# Controller-Board_Rack-PDU_2_1.net
KiCad netlist of a schematic drawn in EAGLE
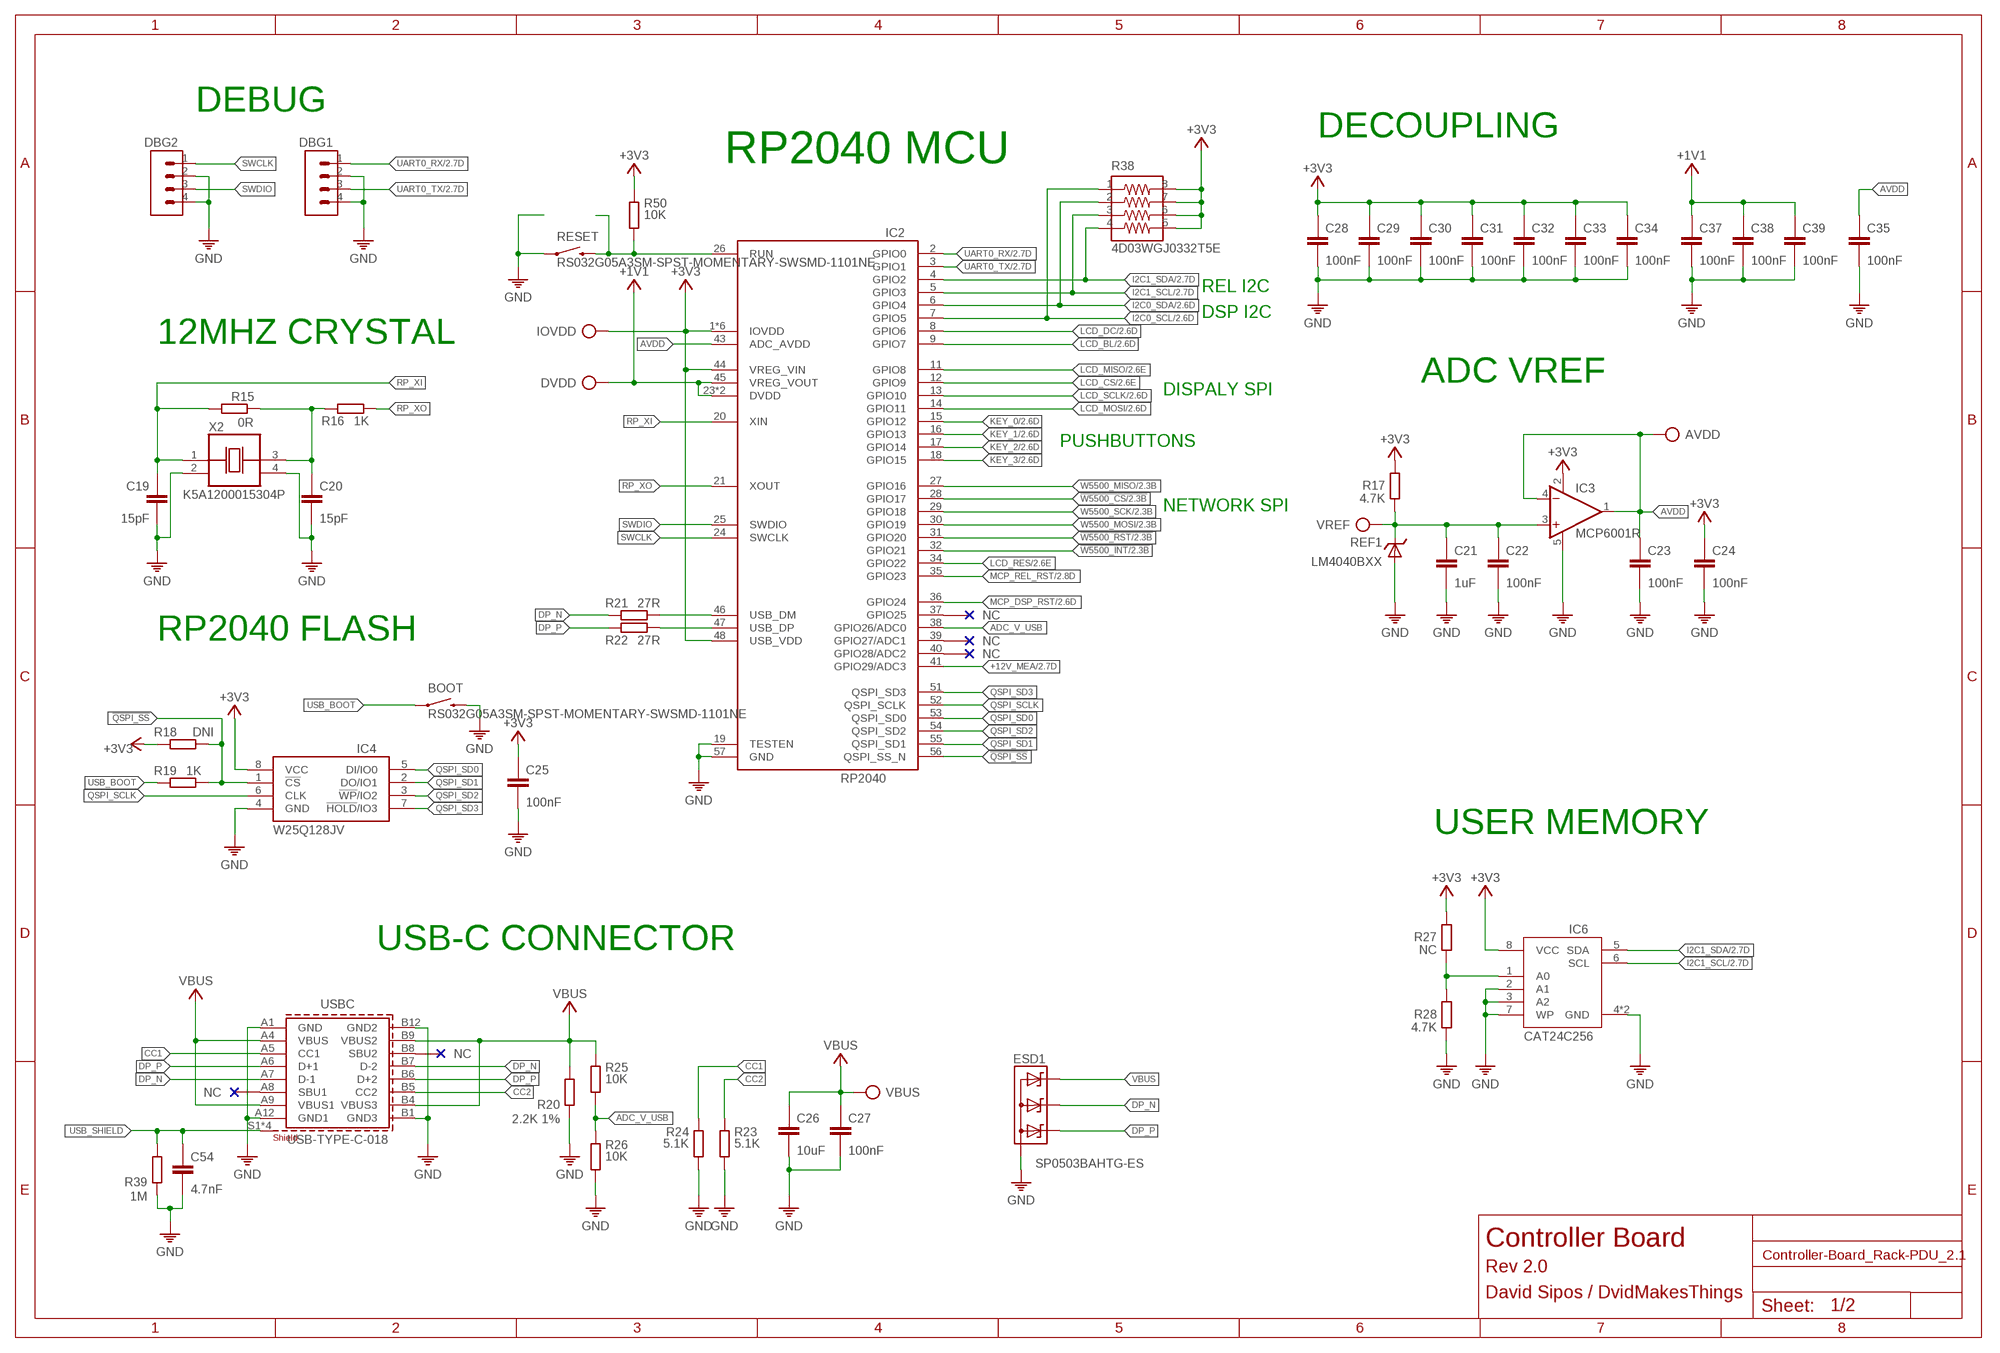
[diagram p0: schematic, sheet 1]
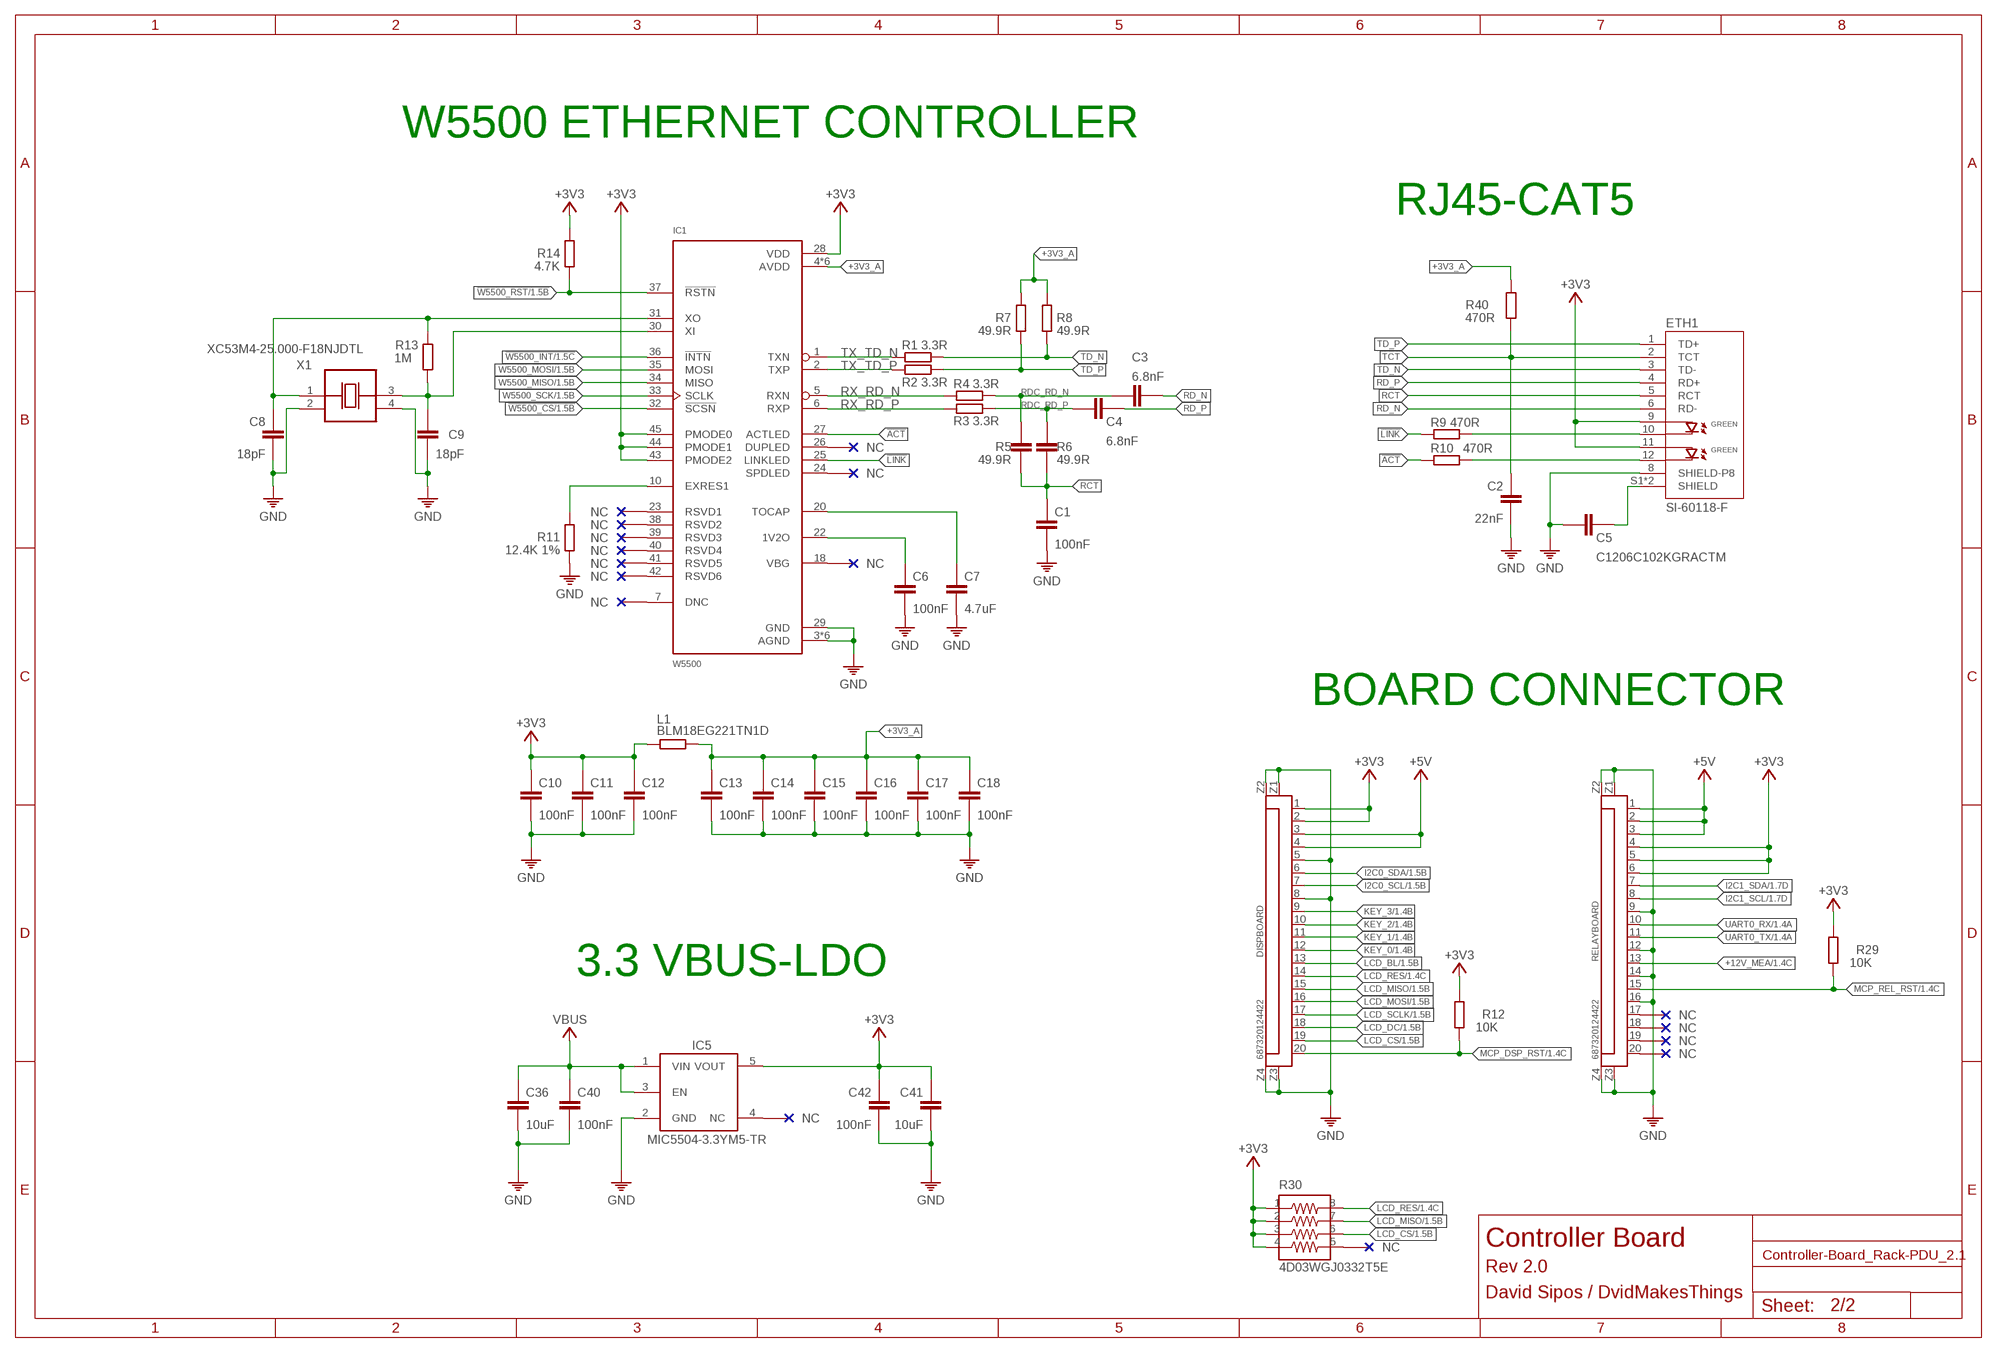
[diagram p1: schematic, sheet 2]

(export (version "E")
  (design (tool "Eeschema 10.0.6"))
  (components
    (comp (ref "C1")
      (value "100nF")
      (footprint "eagle-import:C0402")
      (libsource (lib "eagle-import") (part "C-0402"))
    )
    (comp (ref "C2")
      (value "22nF")
      (footprint "eagle-import:C0402")
      (libsource (lib "eagle-import") (part "C-0402"))
    )
    (comp (ref "C3")
      (value "6.8nF")
      (footprint "eagle-import:C0402")
      (libsource (lib "eagle-import") (part "C-0402"))
    )
    (comp (ref "C4")
      (value "6.8nF")
      (footprint "eagle-import:C0402")
      (libsource (lib "eagle-import") (part "C-0402"))
    )
    (comp (ref "C5")
      (value "C1206C102KGRACTM")
      (footprint "eagle-import:C1206")
      (libsource (lib "eagle-import") (part "C-1206"))
    )
    (comp (ref "C6")
      (value "100nF")
      (footprint "eagle-import:C0402")
      (libsource (lib "eagle-import") (part "C-0402"))
    )
    (comp (ref "C7")
      (value "4.7uF")
      (footprint "eagle-import:C0402")
      (libsource (lib "eagle-import") (part "C-0402"))
    )
    (comp (ref "C8")
      (value "18pF")
      (footprint "eagle-import:C0402")
      (libsource (lib "eagle-import") (part "C-0402"))
    )
    (comp (ref "C9")
      (value "18pF")
      (footprint "eagle-import:C0402")
      (libsource (lib "eagle-import") (part "C-0402"))
    )
    (comp (ref "C10")
      (value "100nF")
      (footprint "eagle-import:C0402")
      (libsource (lib "eagle-import") (part "C-0402"))
    )
    (comp (ref "C11")
      (value "100nF")
      (footprint "eagle-import:C0402")
      (libsource (lib "eagle-import") (part "C-0402"))
    )
    (comp (ref "C12")
      (value "100nF")
      (footprint "eagle-import:C0402")
      (libsource (lib "eagle-import") (part "C-0402"))
    )
    (comp (ref "C13")
      (value "100nF")
      (footprint "eagle-import:C0402")
      (libsource (lib "eagle-import") (part "C-0402"))
    )
    (comp (ref "C14")
      (value "100nF")
      (footprint "eagle-import:C0402")
      (libsource (lib "eagle-import") (part "C-0402"))
    )
    (comp (ref "C15")
      (value "100nF")
      (footprint "eagle-import:C0402")
      (libsource (lib "eagle-import") (part "C-0402"))
    )
    (comp (ref "C16")
      (value "100nF")
      (footprint "eagle-import:C0402")
      (libsource (lib "eagle-import") (part "C-0402"))
    )
    (comp (ref "C17")
      (value "100nF")
      (footprint "eagle-import:C0402")
      (libsource (lib "eagle-import") (part "C-0402"))
    )
    (comp (ref "C18")
      (value "100nF")
      (footprint "eagle-import:C0402")
      (libsource (lib "eagle-import") (part "C-0402"))
    )
    (comp (ref "C36")
      (value "10uF")
      (footprint "eagle-import:0805")
      (libsource (lib "eagle-import") (part "C0805"))
    )
    (comp (ref "C40")
      (value "100nF")
      (footprint "eagle-import:0402")
      (libsource (lib "eagle-import") (part "C0402"))
    )
    (comp (ref "C41")
      (value "10uF")
      (footprint "eagle-import:0805")
      (libsource (lib "eagle-import") (part "C0805"))
    )
    (comp (ref "C42")
      (value "100nF")
      (footprint "eagle-import:0402")
      (libsource (lib "eagle-import") (part "C0402"))
    )
    (comp (ref "DISPBOARD")
      (value "687320124422")
      (footprint "eagle-import:687320124422")
      (libsource (lib "eagle-import") (part "6873XX124422_687320124422"))
    )
    (comp (ref "ETH1")
      (value "SI-60118-F")
      (footprint "eagle-import:RJ45-CAT5")
      (fields (field (name "MANUFACTURER") "Bel Fuse"))
      (libsource (lib "eagle-import") (part "RJ45-CAT5"))
    )
    (comp (ref "IC1")
      (value "W5500")
      (footprint "eagle-import:LQFP48")
      (libsource (lib "eagle-import") (part "W5500"))
    )
    (comp (ref "IC5")
      (value "MIC5504-3.3YM5-TR")
      (footprint "eagle-import:SOT23-5")
      (libsource (lib "eagle-import") (part "MIC5504-3.3YM5-TR"))
    )
    (comp (ref "L1")
      (value "BLM18EG221TN1D")
      (footprint "eagle-import:0603")
      (libsource (lib "eagle-import") (part "R0603"))
    )
    (comp (ref "R1")
      (value "3.3R")
      (footprint "eagle-import:0402")
      (libsource (lib "eagle-import") (part "R0402"))
    )
    (comp (ref "R2")
      (value "3.3R")
      (footprint "eagle-import:0402")
      (libsource (lib "eagle-import") (part "R0402"))
    )
    (comp (ref "R3")
      (value "3.3R")
      (footprint "eagle-import:0402")
      (libsource (lib "eagle-import") (part "R0402"))
    )
    (comp (ref "R4")
      (value "3.3R")
      (footprint "eagle-import:0402")
      (libsource (lib "eagle-import") (part "R0402"))
    )
    (comp (ref "R5")
      (value "49.9R")
      (footprint "eagle-import:C0402")
      (libsource (lib "eagle-import") (part "C-0402"))
    )
    (comp (ref "R6")
      (value "49.9R")
      (footprint "eagle-import:C0402")
      (libsource (lib "eagle-import") (part "C-0402"))
    )
    (comp (ref "R7")
      (value "49.9R")
      (footprint "eagle-import:0402")
      (libsource (lib "eagle-import") (part "R0402"))
    )
    (comp (ref "R8")
      (value "49.9R")
      (footprint "eagle-import:0402")
      (libsource (lib "eagle-import") (part "R0402"))
    )
    (comp (ref "R9")
      (value "470R")
      (footprint "eagle-import:0402")
      (libsource (lib "eagle-import") (part "R0402"))
    )
    (comp (ref "R10")
      (value "470R")
      (footprint "eagle-import:0402")
      (libsource (lib "eagle-import") (part "R0402"))
    )
    (comp (ref "R11")
      (value "12.4K 1%")
      (footprint "eagle-import:0402")
      (libsource (lib "eagle-import") (part "R0402"))
    )
    (comp (ref "R12")
      (value "10K")
      (footprint "eagle-import:0402")
      (libsource (lib "eagle-import") (part "R0402"))
    )
    (comp (ref "R13")
      (value "1M")
      (footprint "eagle-import:0402")
      (libsource (lib "eagle-import") (part "R0402"))
    )
    (comp (ref "R14")
      (value "4.7K")
      (footprint "eagle-import:0402")
      (libsource (lib "eagle-import") (part "R0402"))
    )
    (comp (ref "R29")
      (value "10K")
      (footprint "eagle-import:0402")
      (libsource (lib "eagle-import") (part "R0402"))
    )
    (comp (ref "R30")
      (value "4D03WGJ0332T5E")
      (footprint "eagle-import:742C083103JP")
      (fields
        (field (name "MANUFACTURER") "CTS Resistor Products")
        (field (name "MPN") "742C083103JP")
        (field (name "CREATED_BY") "PCBLayout.com")
      )
      (libsource (lib "eagle-import") (part "742C083103JP"))
    )
    (comp (ref "R40")
      (value "470R")
      (footprint "eagle-import:0402")
      (libsource (lib "eagle-import") (part "R0402"))
    )
    (comp (ref "RELAYBOARD")
      (value "687320124422")
      (footprint "eagle-import:687320124422")
      (libsource (lib "eagle-import") (part "6873XX124422_687320124422"))
    )
    (comp (ref "X1")
      (value "XC53M4-25.000-F18NJDTL")
      (footprint "eagle-import:OSCCC500X320X130")
      (libsource (lib "eagle-import") (part "CRYSTAL"))
    )
    (comp (ref "AVDD")
      (value "TP")
      (footprint "eagle-import:TP")
      (libsource (lib "eagle-import") (part "TP"))
    )
    (comp (ref "BOOT")
      (value "RS032G05A3SM-SPST-MOMENTARY-SWSMD-1101NE")
      (footprint "eagle-import:TACTILE-SWITCH-1101NE")
      (libsource (lib "eagle-import") (part "RS032G05A3SM-SPST-MOMENTARY-SWSMD-1101NE"))
    )
    (comp (ref "C19")
      (value "15pF")
      (footprint "eagle-import:C0402")
      (libsource (lib "eagle-import") (part "C-0402"))
    )
    (comp (ref "C20")
      (value "15pF")
      (footprint "eagle-import:C0402")
      (libsource (lib "eagle-import") (part "C-0402"))
    )
    (comp (ref "C21")
      (value "1uF")
      (footprint "eagle-import:C0402")
      (libsource (lib "eagle-import") (part "C-0402"))
    )
    (comp (ref "C22")
      (value "100nF")
      (footprint "eagle-import:C0402")
      (libsource (lib "eagle-import") (part "C-0402"))
    )
    (comp (ref "C23")
      (value "100nF")
      (footprint "eagle-import:C0402")
      (libsource (lib "eagle-import") (part "C-0402"))
    )
    (comp (ref "C24")
      (value "100nF")
      (footprint "eagle-import:C0402")
      (libsource (lib "eagle-import") (part "C-0402"))
    )
    (comp (ref "C25")
      (value "100nF")
      (footprint "eagle-import:C0402")
      (libsource (lib "eagle-import") (part "C-0402"))
    )
    (comp (ref "C26")
      (value "10uF")
      (footprint "eagle-import:0805")
      (libsource (lib "eagle-import") (part "C0805"))
    )
    (comp (ref "C27")
      (value "100nF")
      (footprint "eagle-import:0402")
      (libsource (lib "eagle-import") (part "C0402"))
    )
    (comp (ref "C28")
      (value "100nF")
      (footprint "eagle-import:C0402")
      (libsource (lib "eagle-import") (part "C-0402"))
    )
    (comp (ref "C29")
      (value "100nF")
      (footprint "eagle-import:C0402")
      (libsource (lib "eagle-import") (part "C-0402"))
    )
    (comp (ref "C30")
      (value "100nF")
      (footprint "eagle-import:C0402")
      (libsource (lib "eagle-import") (part "C-0402"))
    )
    (comp (ref "C31")
      (value "100nF")
      (footprint "eagle-import:C0402")
      (libsource (lib "eagle-import") (part "C-0402"))
    )
    (comp (ref "C32")
      (value "100nF")
      (footprint "eagle-import:C0402")
      (libsource (lib "eagle-import") (part "C-0402"))
    )
    (comp (ref "C33")
      (value "100nF")
      (footprint "eagle-import:C0402")
      (libsource (lib "eagle-import") (part "C-0402"))
    )
    (comp (ref "C34")
      (value "100nF")
      (footprint "eagle-import:C0402")
      (libsource (lib "eagle-import") (part "C-0402"))
    )
    (comp (ref "C35")
      (value "100nF")
      (footprint "eagle-import:C0402")
      (libsource (lib "eagle-import") (part "C-0402"))
    )
    (comp (ref "C37")
      (value "100nF")
      (footprint "eagle-import:C0402")
      (libsource (lib "eagle-import") (part "C-0402"))
    )
    (comp (ref "C38")
      (value "100nF")
      (footprint "eagle-import:C0402")
      (libsource (lib "eagle-import") (part "C-0402"))
    )
    (comp (ref "C39")
      (value "100nF")
      (footprint "eagle-import:C0402")
      (libsource (lib "eagle-import") (part "C-0402"))
    )
    (comp (ref "C54")
      (value "4.7nF")
      (footprint "eagle-import:0402")
      (libsource (lib "eagle-import") (part "C0402"))
    )
    (comp (ref "DBG1")
      (value "CON-1X4")
      (footprint "eagle-import:1X4")
      (libsource (lib "eagle-import") (part "CON-1X4"))
    )
    (comp (ref "DBG2")
      (value "CON-1X4")
      (footprint "eagle-import:1X4")
      (libsource (lib "eagle-import") (part "CON-1X4"))
    )
    (comp (ref "DVDD")
      (value "TP")
      (footprint "eagle-import:TP")
      (libsource (lib "eagle-import") (part "TP"))
    )
    (comp (ref "ESD1")
      (value "SP0503BAHTG-ES")
      (footprint "eagle-import:SOT143")
      (libsource (lib "eagle-import") (part "SP0503BAHT"))
    )
    (comp (ref "IC2")
      (value "RP2040")
      (footprint "eagle-import:QFN40P700X700X100-57T510")
      (libsource (lib "eagle-import") (part "RP2040"))
    )
    (comp (ref "IC3")
      (value "MCP6001R")
      (footprint "eagle-import:SOT23-5")
      (libsource (lib "eagle-import") (part "MCP6001RT"))
    )
    (comp (ref "IC4")
      (value "W25Q128JVPIQ")
      (footprint "eagle-import:SON127P600X500X75-8N")
      (libsource (lib "eagle-import") (part "W25Q128JVP"))
    )
    (comp (ref "IC6")
      (value "CAT24C512HU5IGT3")
      (footprint "eagle-import:SON50P300X200X50-9T130X140N")
      (libsource (lib "eagle-import") (part "CAT24C256-HU4"))
    )
    (comp (ref "IOVDD")
      (value "TP")
      (footprint "eagle-import:TP")
      (libsource (lib "eagle-import") (part "TP"))
    )
    (comp (ref "R15")
      (value "0R")
      (footprint "eagle-import:0402")
      (libsource (lib "eagle-import") (part "R0402"))
    )
    (comp (ref "R16")
      (value "1K")
      (footprint "eagle-import:0402")
      (libsource (lib "eagle-import") (part "R0402"))
    )
    (comp (ref "R17")
      (value "4.7K")
      (footprint "eagle-import:0402")
      (libsource (lib "eagle-import") (part "R0402"))
    )
    (comp (ref "R18")
      (value "DNI")
      (footprint "eagle-import:0402")
      (libsource (lib "eagle-import") (part "R0402"))
    )
    (comp (ref "R19")
      (value "1K")
      (footprint "eagle-import:0402")
      (libsource (lib "eagle-import") (part "R0402"))
    )
    (comp (ref "R20")
      (value "2.2K 1%")
      (footprint "eagle-import:0402")
      (libsource (lib "eagle-import") (part "ds_passive_46685041_R0402"))
    )
    (comp (ref "R21")
      (value "27R")
      (footprint "eagle-import:R0201")
      (libsource (lib "eagle-import") (part "R0201"))
    )
    (comp (ref "R22")
      (value "27R")
      (footprint "eagle-import:R0201")
      (libsource (lib "eagle-import") (part "R0201"))
    )
    (comp (ref "R23")
      (value "5.1K")
      (footprint "eagle-import:0402")
      (libsource (lib "eagle-import") (part "ds_passive_46685041_R0402"))
    )
    (comp (ref "R24")
      (value "5.1K")
      (footprint "eagle-import:0402")
      (libsource (lib "eagle-import") (part "ds_passive_46685041_R0402"))
    )
    (comp (ref "R25")
      (value "10K")
      (footprint "eagle-import:0402")
      (libsource (lib "eagle-import") (part "ds_passive_46685041_R0402"))
    )
    (comp (ref "R26")
      (value "10K")
      (footprint "eagle-import:0402")
      (libsource (lib "eagle-import") (part "ds_passive_46685041_R0402"))
    )
    (comp (ref "R27")
      (value "NC")
      (footprint "eagle-import:0402")
      (libsource (lib "eagle-import") (part "R0402"))
    )
    (comp (ref "R28")
      (value "4.7K")
      (footprint "eagle-import:0402")
      (libsource (lib "eagle-import") (part "R0402"))
    )
    (comp (ref "R38")
      (value "4D03WGJ0332T5E")
      (footprint "eagle-import:742C083103JP")
      (fields
        (field (name "MANUFACTURER") "CTS Resistor Products")
        (field (name "MPN") "742C083103JP")
        (field (name "CREATED_BY") "PCBLayout.com")
      )
      (libsource (lib "eagle-import") (part "742C083103JP"))
    )
    (comp (ref "R39")
      (value "1M")
      (footprint "eagle-import:0402")
      (libsource (lib "eagle-import") (part "ds_passive_46685041_R0402"))
    )
    (comp (ref "R50")
      (value "10K")
      (footprint "eagle-import:0402")
      (libsource (lib "eagle-import") (part "ds_passive_46685041_R0402"))
    )
    (comp (ref "REF1")
      (value "LM4040BXX")
      (footprint "eagle-import:SOT23")
      (libsource (lib "eagle-import") (part "LM4040BXX"))
    )
    (comp (ref "RESET")
      (value "RS032G05A3SM-SPST-MOMENTARY-SWSMD-1101NE")
      (footprint "eagle-import:TACTILE-SWITCH-1101NE")
      (libsource (lib "eagle-import") (part "RS032G05A3SM-SPST-MOMENTARY-SWSMD-1101NE"))
    )
    (comp (ref "USBC")
      (value "USB-TYPE-C-018")
      (footprint "eagle-import:629722000214")
      (libsource (lib "eagle-import") (part "629722000214"))
    )
    (comp (ref "VBUS")
      (value "TP")
      (footprint "eagle-import:TP")
      (libsource (lib "eagle-import") (part "TP"))
    )
    (comp (ref "VREF")
      (value "TP")
      (footprint "eagle-import:TP")
      (libsource (lib "eagle-import") (part "TP"))
    )
    (comp (ref "X2")
      (value "K5A1200015304P")
      (footprint "eagle-import:OSCCC500X320X130")
      (libsource (lib "eagle-import") (part "CRYSTAL"))
    )
  )
  (nets
    (net (code "1") (name "+1V1") (class "Default")
      (node (ref "C37") (pin "1") (pinfunction "1_1") (pintype "passive"))
      (node (ref "C38") (pin "1") (pinfunction "1_1") (pintype "passive"))
      (node (ref "C39") (pin "1") (pinfunction "1_1") (pintype "passive"))
      (node (ref "DVDD") (pin "TP") (pinfunction "P$1_TP") (pintype "bidirectional"))
      (node (ref "IC2") (pin "23") (pinfunction "DVDD_23") (pintype "bidirectional"))
      (node (ref "IC2") (pin "45") (pinfunction "VREG_VOUT_45") (pintype "bidirectional"))
      (node (ref "IC2") (pin "50") (pinfunction "DVDD_50") (pintype "bidirectional"))
    )
    (net (code "2") (name "+3V3") (class "Default")
      (node (ref "C10") (pin "1") (pinfunction "1_1") (pintype "passive"))
      (node (ref "C11") (pin "1") (pinfunction "1_1") (pintype "passive"))
      (node (ref "C12") (pin "1") (pinfunction "1_1") (pintype "passive"))
      (node (ref "C24") (pin "1") (pinfunction "1_1") (pintype "passive"))
      (node (ref "C25") (pin "1") (pinfunction "1_1") (pintype "passive"))
      (node (ref "C28") (pin "1") (pinfunction "1_1") (pintype "passive"))
      (node (ref "C29") (pin "1") (pinfunction "1_1") (pintype "passive"))
      (node (ref "C30") (pin "1") (pinfunction "1_1") (pintype "passive"))
      (node (ref "C31") (pin "1") (pinfunction "1_1") (pintype "passive"))
      (node (ref "C32") (pin "1") (pinfunction "1_1") (pintype "passive"))
      (node (ref "C33") (pin "1") (pinfunction "1_1") (pintype "passive"))
      (node (ref "C34") (pin "1") (pinfunction "1_1") (pintype "passive"))
      (node (ref "C41") (pin "1") (pinfunction "1_1") (pintype "passive"))
      (node (ref "C42") (pin "1") (pinfunction "1_1") (pintype "passive"))
      (node (ref "DISPBOARD") (pin "1") (pinfunction "1_1") (pintype "passive"))
      (node (ref "DISPBOARD") (pin "2") (pinfunction "2_2") (pintype "passive"))
      (node (ref "ETH1") (pin "11") (pinfunction "GA2_11") (pintype "passive"))
      (node (ref "ETH1") (pin "9") (pinfunction "GA1_9") (pintype "passive"))
      (node (ref "IC1") (pin "28") (pinfunction "VDD_28") (pintype "power_in"))
      (node (ref "IC1") (pin "43") (pinfunction "PMODE2_43") (pintype "input"))
      (node (ref "IC1") (pin "44") (pinfunction "PMODE1_44") (pintype "input"))
      (node (ref "IC1") (pin "45") (pinfunction "PMODE0_45") (pintype "input"))
      (node (ref "IC2") (pin "1") (pinfunction "IOVDD_1") (pintype "bidirectional"))
      (node (ref "IC2") (pin "10") (pinfunction "IOVDD_10") (pintype "bidirectional"))
      (node (ref "IC2") (pin "22") (pinfunction "IOVDD_22") (pintype "bidirectional"))
      (node (ref "IC2") (pin "33") (pinfunction "IOVDD_33") (pintype "bidirectional"))
      (node (ref "IC2") (pin "42") (pinfunction "IOVDD_42") (pintype "bidirectional"))
      (node (ref "IC2") (pin "44") (pinfunction "VREG_VIN_44") (pintype "bidirectional"))
      (node (ref "IC2") (pin "48") (pinfunction "USB_VDD_48") (pintype "bidirectional"))
      (node (ref "IC2") (pin "49") (pinfunction "IOVDD_49") (pintype "bidirectional"))
      (node (ref "IC3") (pin "2") (pinfunction "V+_2") (pintype "power_in"))
      (node (ref "IC4") (pin "8") (pinfunction "VCC_8") (pintype "power_in"))
      (node (ref "IC5") (pin "5") (pinfunction "VOUT_5") (pintype "bidirectional"))
      (node (ref "IC6") (pin "8") (pinfunction "VCC_8") (pintype "power_in"))
      (node (ref "IOVDD") (pin "TP") (pinfunction "P$1_TP") (pintype "bidirectional"))
      (node (ref "L1") (pin "1") (pinfunction "1_1") (pintype "passive"))
      (node (ref "R12") (pin "2") (pinfunction "2_2") (pintype "passive"))
      (node (ref "R14") (pin "2") (pinfunction "2_2") (pintype "passive"))
      (node (ref "R17") (pin "2") (pinfunction "2_2") (pintype "passive"))
      (node (ref "R18") (pin "2") (pinfunction "2_2") (pintype "passive"))
      (node (ref "R27") (pin "2") (pinfunction "2_2") (pintype "passive"))
      (node (ref "R29") (pin "2") (pinfunction "2_2") (pintype "passive"))
      (node (ref "R30") (pin "1") (pinfunction "1_1") (pintype "passive"))
      (node (ref "R30") (pin "2") (pinfunction "2_2") (pintype "passive"))
      (node (ref "R30") (pin "3") (pinfunction "3_3") (pintype "passive"))
      (node (ref "R30") (pin "4") (pinfunction "4_4") (pintype "passive"))
      (node (ref "R38") (pin "5") (pinfunction "5_5") (pintype "passive"))
      (node (ref "R38") (pin "6") (pinfunction "6_6") (pintype "passive"))
      (node (ref "R38") (pin "7") (pinfunction "7_7") (pintype "passive"))
      (node (ref "R38") (pin "8") (pinfunction "8_8") (pintype "passive"))
      (node (ref "R50") (pin "1") (pinfunction "1_1") (pintype "passive"))
      (node (ref "RELAYBOARD") (pin "4") (pinfunction "4_4") (pintype "passive"))
      (node (ref "RELAYBOARD") (pin "5") (pinfunction "5_5") (pintype "passive"))
      (node (ref "RELAYBOARD") (pin "6") (pinfunction "6_6") (pintype "passive"))
    )
    (net (code "3") (name "+3V3_A") (class "Default")
      (node (ref "C13") (pin "1") (pinfunction "1_1") (pintype "passive"))
      (node (ref "C14") (pin "1") (pinfunction "1_1") (pintype "passive"))
      (node (ref "C15") (pin "1") (pinfunction "1_1") (pintype "passive"))
      (node (ref "C16") (pin "1") (pinfunction "1_1") (pintype "passive"))
      (node (ref "C17") (pin "1") (pinfunction "1_1") (pintype "passive"))
      (node (ref "C18") (pin "1") (pinfunction "1_1") (pintype "passive"))
      (node (ref "IC1") (pin "11") (pinfunction "AVDD_11") (pintype "power_in"))
      (node (ref "IC1") (pin "15") (pinfunction "AVDD_15") (pintype "power_in"))
      (node (ref "IC1") (pin "17") (pinfunction "AVDD_17") (pintype "power_in"))
      (node (ref "IC1") (pin "21") (pinfunction "AVDD_21") (pintype "power_in"))
      (node (ref "IC1") (pin "4") (pinfunction "AVDD_4") (pintype "power_in"))
      (node (ref "IC1") (pin "8") (pinfunction "AVDD_8") (pintype "power_in"))
      (node (ref "L1") (pin "2") (pinfunction "2_2") (pintype "passive"))
      (node (ref "R40") (pin "2") (pinfunction "2_2") (pintype "passive"))
      (node (ref "R7") (pin "2") (pinfunction "2_2") (pintype "passive"))
      (node (ref "R8") (pin "2") (pinfunction "2_2") (pintype "passive"))
    )
    (net (code "4") (name "+5V") (class "Default")
      (node (ref "DISPBOARD") (pin "3") (pinfunction "3_3") (pintype "passive"))
      (node (ref "DISPBOARD") (pin "4") (pinfunction "4_4") (pintype "passive"))
      (node (ref "RELAYBOARD") (pin "1") (pinfunction "1_1") (pintype "passive"))
      (node (ref "RELAYBOARD") (pin "2") (pinfunction "2_2") (pintype "passive"))
      (node (ref "RELAYBOARD") (pin "3") (pinfunction "3_3") (pintype "passive"))
    )
    (net (code "5") (name "+12V_MEA") (class "Default")
      (node (ref "IC2") (pin "41") (pinfunction "GPIO29/ADC3_41") (pintype "bidirectional"))
      (node (ref "RELAYBOARD") (pin "13") (pinfunction "13_13") (pintype "passive"))
    )
    (net (code "6") (name "ADC_V_USB") (class "Default")
      (node (ref "IC2") (pin "38") (pinfunction "GPIO26/ADC0_38") (pintype "bidirectional"))
      (node (ref "R25") (pin "2") (pinfunction "2_2") (pintype "passive"))
      (node (ref "R26") (pin "1") (pinfunction "1_1") (pintype "passive"))
    )
    (net (code "7") (name "AVDD") (class "Default")
      (node (ref "AVDD") (pin "TP") (pinfunction "P$1_TP") (pintype "bidirectional"))
      (node (ref "C23") (pin "1") (pinfunction "1_1") (pintype "passive"))
      (node (ref "C35") (pin "1") (pinfunction "1_1") (pintype "passive"))
      (node (ref "IC2") (pin "43") (pinfunction "ADC_AVDD_43") (pintype "bidirectional"))
      (node (ref "IC3") (pin "1") (pinfunction "OUT_1") (pintype "output"))
      (node (ref "IC3") (pin "4") (pinfunction "-IN_4") (pintype "input"))
    )
    (net (code "8") (name "CC1") (class "Default")
      (node (ref "R24") (pin "1") (pinfunction "1_1") (pintype "passive"))
      (node (ref "USBC") (pin "A5") (pinfunction "CC1_A5") (pintype "passive"))
    )
    (net (code "9") (name "CC2") (class "Default")
      (node (ref "R23") (pin "1") (pinfunction "1_1") (pintype "passive"))
      (node (ref "USBC") (pin "B5") (pinfunction "CC2_B5") (pintype "passive"))
    )
    (net (code "10") (name "DP_N") (class "Default")
      (node (ref "ESD1") (pin "3") (pinfunction "C2_3") (pintype "bidirectional"))
      (node (ref "R21") (pin "1") (pinfunction "1_1") (pintype "passive"))
      (node (ref "USBC") (pin "A7") (pinfunction "D-1_A7") (pintype "passive"))
      (node (ref "USBC") (pin "B7") (pinfunction "D-2_B7") (pintype "passive"))
    )
    (net (code "11") (name "DP_P") (class "Default")
      (node (ref "ESD1") (pin "2") (pinfunction "C1_2") (pintype "bidirectional"))
      (node (ref "R22") (pin "1") (pinfunction "1_1") (pintype "passive"))
      (node (ref "USBC") (pin "A6") (pinfunction "D+1_A6") (pintype "passive"))
      (node (ref "USBC") (pin "B6") (pinfunction "D+2_B6") (pintype "passive"))
    )
    (net (code "12") (name "GND") (class "Default")
      (node (ref "BOOT") (pin "2") (pinfunction "2_2") (pintype "passive"))
      (node (ref "C1") (pin "2") (pinfunction "2_2") (pintype "passive"))
      (node (ref "C10") (pin "2") (pinfunction "2_2") (pintype "passive"))
      (node (ref "C11") (pin "2") (pinfunction "2_2") (pintype "passive"))
      (node (ref "C12") (pin "2") (pinfunction "2_2") (pintype "passive"))
      (node (ref "C13") (pin "2") (pinfunction "2_2") (pintype "passive"))
      (node (ref "C14") (pin "2") (pinfunction "2_2") (pintype "passive"))
      (node (ref "C15") (pin "2") (pinfunction "2_2") (pintype "passive"))
      (node (ref "C16") (pin "2") (pinfunction "2_2") (pintype "passive"))
      (node (ref "C17") (pin "2") (pinfunction "2_2") (pintype "passive"))
      (node (ref "C18") (pin "2") (pinfunction "2_2") (pintype "passive"))
      (node (ref "C19") (pin "2") (pinfunction "2_2") (pintype "passive"))
      (node (ref "C2") (pin "2") (pinfunction "2_2") (pintype "passive"))
      (node (ref "C20") (pin "2") (pinfunction "2_2") (pintype "passive"))
      (node (ref "C21") (pin "2") (pinfunction "2_2") (pintype "passive"))
      (node (ref "C22") (pin "2") (pinfunction "2_2") (pintype "passive"))
      (node (ref "C23") (pin "2") (pinfunction "2_2") (pintype "passive"))
      (node (ref "C24") (pin "2") (pinfunction "2_2") (pintype "passive"))
      (node (ref "C25") (pin "2") (pinfunction "2_2") (pintype "passive"))
      (node (ref "C26") (pin "2") (pinfunction "2_2") (pintype "passive"))
      (node (ref "C27") (pin "2") (pinfunction "2_2") (pintype "passive"))
      (node (ref "C28") (pin "2") (pinfunction "2_2") (pintype "passive"))
      (node (ref "C29") (pin "2") (pinfunction "2_2") (pintype "passive"))
      (node (ref "C30") (pin "2") (pinfunction "2_2") (pintype "passive"))
      (node (ref "C31") (pin "2") (pinfunction "2_2") (pintype "passive"))
      (node (ref "C32") (pin "2") (pinfunction "2_2") (pintype "passive"))
      (node (ref "C33") (pin "2") (pinfunction "2_2") (pintype "passive"))
      (node (ref "C34") (pin "2") (pinfunction "2_2") (pintype "passive"))
      (node (ref "C35") (pin "2") (pinfunction "2_2") (pintype "passive"))
      (node (ref "C36") (pin "2") (pinfunction "2_2") (pintype "passive"))
      (node (ref "C37") (pin "2") (pinfunction "2_2") (pintype "passive"))
      (node (ref "C38") (pin "2") (pinfunction "2_2") (pintype "passive"))
      (node (ref "C39") (pin "2") (pinfunction "2_2") (pintype "passive"))
      (node (ref "C40") (pin "2") (pinfunction "2_2") (pintype "passive"))
      (node (ref "C41") (pin "2") (pinfunction "2_2") (pintype "passive"))
      (node (ref "C42") (pin "2") (pinfunction "2_2") (pintype "passive"))
      (node (ref "C5") (pin "1") (pinfunction "1_1") (pintype "passive"))
      (node (ref "C54") (pin "2") (pinfunction "2_2") (pintype "passive"))
      (node (ref "C6") (pin "2") (pinfunction "2_2") (pintype "passive"))
      (node (ref "C7") (pin "2") (pinfunction "2_2") (pintype "passive"))
      (node (ref "C8") (pin "2") (pinfunction "2_2") (pintype "passive"))
      (node (ref "C9") (pin "2") (pinfunction "2_2") (pintype "passive"))
      (node (ref "DBG1") (pin "2") (pinfunction "P$2_2") (pintype "bidirectional"))
      (node (ref "DBG1") (pin "4") (pinfunction "P$4_4") (pintype "bidirectional"))
      (node (ref "DBG2") (pin "2") (pinfunction "P$2_2") (pintype "bidirectional"))
      (node (ref "DBG2") (pin "4") (pinfunction "P$4_4") (pintype "bidirectional"))
      (node (ref "DISPBOARD") (pin "5") (pinfunction "5_5") (pintype "passive"))
      (node (ref "DISPBOARD") (pin "8") (pinfunction "8_8") (pintype "passive"))
      (node (ref "DISPBOARD") (pin "Z1") (pinfunction "Z1_Z1") (pintype "passive"))
      (node (ref "DISPBOARD") (pin "Z2") (pinfunction "Z2_Z2") (pintype "passive"))
      (node (ref "DISPBOARD") (pin "Z3") (pinfunction "Z3_Z3") (pintype "passive"))
      (node (ref "DISPBOARD") (pin "Z4") (pinfunction "Z4_Z4") (pintype "passive"))
      (node (ref "ESD1") (pin "1") (pinfunction "A_1") (pintype "bidirectional"))
      (node (ref "ETH1") (pin "8") (pinfunction "SHIELD-P8_8") (pintype "passive"))
      (node (ref "IC1") (pin "14") (pinfunction "AGND_14") (pintype "power_in"))
      (node (ref "IC1") (pin "16") (pinfunction "AGND_16") (pintype "power_in"))
      (node (ref "IC1") (pin "19") (pinfunction "AGND_19") (pintype "power_in"))
      (node (ref "IC1") (pin "29") (pinfunction "GND_29") (pintype "passive"))
      (node (ref "IC1") (pin "3") (pinfunction "AGND_3") (pintype "power_in"))
      (node (ref "IC1") (pin "48") (pinfunction "AGND_48") (pintype "power_in"))
      (node (ref "IC1") (pin "9") (pinfunction "AGND_9") (pintype "power_in"))
      (node (ref "IC2") (pin "19") (pinfunction "TESTEN_19") (pintype "bidirectional"))
      (node (ref "IC2") (pin "57") (pinfunction "GND_57") (pintype "bidirectional"))
      (node (ref "IC3") (pin "5") (pinfunction "V-_5") (pintype "power_in"))
      (node (ref "IC4") (pin "4") (pinfunction "GND_4") (pintype "power_in"))
      (node (ref "IC5") (pin "2") (pinfunction "GND_2") (pintype "bidirectional"))
      (node (ref "IC6") (pin "2") (pinfunction "A1_2") (pintype "bidirectional"))
      (node (ref "IC6") (pin "3") (pinfunction "A2_3") (pintype "bidirectional"))
      (node (ref "IC6") (pin "4") (pinfunction "GND_4") (pintype "power_in"))
      (node (ref "IC6") (pin "7") (pinfunction "WP_7") (pintype "bidirectional"))
      (node (ref "IC6") (pin "9") (pinfunction "GND_9") (pintype "power_in"))
      (node (ref "R11") (pin "1") (pinfunction "1_1") (pintype "passive"))
      (node (ref "R20") (pin "2") (pinfunction "2_2") (pintype "passive"))
      (node (ref "R23") (pin "2") (pinfunction "2_2") (pintype "passive"))
      (node (ref "R24") (pin "2") (pinfunction "2_2") (pintype "passive"))
      (node (ref "R26") (pin "2") (pinfunction "2_2") (pintype "passive"))
      (node (ref "R28") (pin "1") (pinfunction "1_1") (pintype "passive"))
      (node (ref "R39") (pin "2") (pinfunction "2_2") (pintype "passive"))
      (node (ref "REF1") (pin "2") (pinfunction "A_2") (pintype "passive"))
      (node (ref "REF1") (pin "3") (pinfunction "A_3") (pintype "passive"))
      (node (ref "RELAYBOARD") (pin "12") (pinfunction "12_12") (pintype "passive"))
      (node (ref "RELAYBOARD") (pin "14") (pinfunction "14_14") (pintype "passive"))
      (node (ref "RELAYBOARD") (pin "16") (pinfunction "16_16") (pintype "passive"))
      (node (ref "RELAYBOARD") (pin "9") (pinfunction "9_9") (pintype "passive"))
      (node (ref "RELAYBOARD") (pin "Z1") (pinfunction "Z1_Z1") (pintype "passive"))
      (node (ref "RELAYBOARD") (pin "Z2") (pinfunction "Z2_Z2") (pintype "passive"))
      (node (ref "RELAYBOARD") (pin "Z3") (pinfunction "Z3_Z3") (pintype "passive"))
      (node (ref "RELAYBOARD") (pin "Z4") (pinfunction "Z4_Z4") (pintype "passive"))
      (node (ref "RESET") (pin "1") (pinfunction "1_1") (pintype "passive"))
      (node (ref "USBC") (pin "A1") (pinfunction "GND_A1") (pintype "passive"))
      (node (ref "USBC") (pin "A12") (pinfunction "GND1_A12") (pintype "passive"))
      (node (ref "USBC") (pin "B1") (pinfunction "GND3_B1") (pintype "passive"))
      (node (ref "USBC") (pin "B12") (pinfunction "GND2_B12") (pintype "passive"))
      (node (ref "X1") (pin "2") (pinfunction "VSS_2") (pintype "power_in"))
      (node (ref "X1") (pin "4") (pinfunction "VDD_4") (pintype "power_in"))
      (node (ref "X2") (pin "2") (pinfunction "VSS_2") (pintype "power_in"))
      (node (ref "X2") (pin "4") (pinfunction "VDD_4") (pintype "power_in"))
    )
    (net (code "13") (name "I2C0_SCL") (class "Default")
      (node (ref "DISPBOARD") (pin "7") (pinfunction "7_7") (pintype "passive"))
      (node (ref "IC2") (pin "7") (pinfunction "GPIO5_7") (pintype "bidirectional"))
      (node (ref "R38") (pin "1") (pinfunction "1_1") (pintype "passive"))
    )
    (net (code "14") (name "I2C0_SDA") (class "Default")
      (node (ref "DISPBOARD") (pin "6") (pinfunction "6_6") (pintype "passive"))
      (node (ref "IC2") (pin "6") (pinfunction "GPIO4_6") (pintype "bidirectional"))
      (node (ref "R38") (pin "2") (pinfunction "2_2") (pintype "passive"))
    )
    (net (code "15") (name "I2C1_SCL") (class "Default")
      (node (ref "IC2") (pin "5") (pinfunction "GPIO3_5") (pintype "bidirectional"))
      (node (ref "IC6") (pin "6") (pinfunction "SCL_6") (pintype "bidirectional"))
      (node (ref "R38") (pin "3") (pinfunction "3_3") (pintype "passive"))
      (node (ref "RELAYBOARD") (pin "8") (pinfunction "8_8") (pintype "passive"))
    )
    (net (code "16") (name "I2C1_SDA") (class "Default")
      (node (ref "IC2") (pin "4") (pinfunction "GPIO2_4") (pintype "bidirectional"))
      (node (ref "IC6") (pin "5") (pinfunction "SDA_5") (pintype "bidirectional"))
      (node (ref "R38") (pin "4") (pinfunction "4_4") (pintype "passive"))
      (node (ref "RELAYBOARD") (pin "7") (pinfunction "7_7") (pintype "passive"))
    )
    (net (code "17") (name "KEY_0") (class "Default")
      (node (ref "DISPBOARD") (pin "12") (pinfunction "12_12") (pintype "passive"))
      (node (ref "IC2") (pin "15") (pinfunction "GPIO12_15") (pintype "bidirectional"))
    )
    (net (code "18") (name "KEY_1") (class "Default")
      (node (ref "DISPBOARD") (pin "11") (pinfunction "11_11") (pintype "passive"))
      (node (ref "IC2") (pin "16") (pinfunction "GPIO13_16") (pintype "bidirectional"))
    )
    (net (code "19") (name "KEY_2") (class "Default")
      (node (ref "DISPBOARD") (pin "10") (pinfunction "10_10") (pintype "passive"))
      (node (ref "IC2") (pin "17") (pinfunction "GPIO14_17") (pintype "bidirectional"))
    )
    (net (code "20") (name "KEY_3") (class "Default")
      (node (ref "DISPBOARD") (pin "9") (pinfunction "9_9") (pintype "passive"))
      (node (ref "IC2") (pin "18") (pinfunction "GPIO15_18") (pintype "bidirectional"))
    )
    (net (code "21") (name "LCD_BL") (class "Default")
      (node (ref "DISPBOARD") (pin "13") (pinfunction "13_13") (pintype "passive"))
      (node (ref "IC2") (pin "9") (pinfunction "GPIO7_9") (pintype "bidirectional"))
    )
    (net (code "22") (name "LCD_CS") (class "Default")
      (node (ref "DISPBOARD") (pin "19") (pinfunction "19_19") (pintype "passive"))
      (node (ref "IC2") (pin "12") (pinfunction "GPIO9_12") (pintype "bidirectional"))
      (node (ref "R30") (pin "6") (pinfunction "6_6") (pintype "passive"))
    )
    (net (code "23") (name "LCD_DC") (class "Default")
      (node (ref "DISPBOARD") (pin "18") (pinfunction "18_18") (pintype "passive"))
      (node (ref "IC2") (pin "8") (pinfunction "GPIO6_8") (pintype "bidirectional"))
    )
    (net (code "24") (name "LCD_MISO") (class "Default")
      (node (ref "DISPBOARD") (pin "15") (pinfunction "15_15") (pintype "passive"))
      (node (ref "IC2") (pin "11") (pinfunction "GPIO8_11") (pintype "bidirectional"))
      (node (ref "R30") (pin "7") (pinfunction "7_7") (pintype "passive"))
    )
    (net (code "25") (name "LCD_MOSI") (class "Default")
      (node (ref "DISPBOARD") (pin "16") (pinfunction "16_16") (pintype "passive"))
      (node (ref "IC2") (pin "14") (pinfunction "GPIO11_14") (pintype "bidirectional"))
    )
    (net (code "26") (name "LCD_RES") (class "Default")
      (node (ref "DISPBOARD") (pin "14") (pinfunction "14_14") (pintype "passive"))
      (node (ref "IC2") (pin "34") (pinfunction "GPIO22_34") (pintype "bidirectional"))
      (node (ref "R30") (pin "8") (pinfunction "8_8") (pintype "passive"))
    )
    (net (code "27") (name "LCD_SCLK") (class "Default")
      (node (ref "DISPBOARD") (pin "17") (pinfunction "17_17") (pintype "passive"))
      (node (ref "IC2") (pin "13") (pinfunction "GPIO10_13") (pintype "bidirectional"))
    )
    (net (code "28") (name "MCP_DSP_RST") (class "Default")
      (node (ref "DISPBOARD") (pin "20") (pinfunction "20_20") (pintype "passive"))
      (node (ref "IC2") (pin "36") (pinfunction "GPIO24_36") (pintype "bidirectional"))
      (node (ref "R12") (pin "1") (pinfunction "1_1") (pintype "passive"))
    )
    (net (code "29") (name "MCP_REL_RST") (class "Default")
      (node (ref "IC2") (pin "35") (pinfunction "GPIO23_35") (pintype "bidirectional"))
      (node (ref "R29") (pin "1") (pinfunction "1_1") (pintype "passive"))
      (node (ref "RELAYBOARD") (pin "15") (pinfunction "15_15") (pintype "passive"))
    )
    (net (code "30") (name "Net-(C5-Pad2)") (class "Default")
      (node (ref "C5") (pin "2") (pinfunction "2_2") (pintype "passive"))
      (node (ref "ETH1") (pin "S1") (pinfunction "SHIELD_S1") (pintype "passive"))
      (node (ref "ETH1") (pin "S2") (pinfunction "SHIELD_S2") (pintype "passive"))
    )
    (net (code "31") (name "Net-(ETH1-GK1)") (class "Default")
      (node (ref "ETH1") (pin "10") (pinfunction "GK1_10") (pintype "passive"))
      (node (ref "R9") (pin "2") (pinfunction "2_2") (pintype "passive"))
    )
    (net (code "32") (name "Net-(ETH1-GK2)") (class "Default")
      (node (ref "ETH1") (pin "12") (pinfunction "GK2_12") (pintype "passive"))
      (node (ref "R10") (pin "2") (pinfunction "2_2") (pintype "passive"))
    )
    (net (code "33") (name "Net-(IC1-1V2O)") (class "Default")
      (node (ref "C6") (pin "1") (pinfunction "1_1") (pintype "passive"))
      (node (ref "IC1") (pin "22") (pinfunction "1V2O_22") (pintype "output"))
    )
    (net (code "34") (name "Net-(IC1-EXRES1)") (class "Default")
      (node (ref "IC1") (pin "10") (pinfunction "EXRES1_10") (pintype "bidirectional"))
      (node (ref "R11") (pin "2") (pinfunction "2_2") (pintype "passive"))
    )
    (net (code "35") (name "Net-(IC1-TOCAP)") (class "Default")
      (node (ref "C7") (pin "1") (pinfunction "1_1") (pintype "passive"))
      (node (ref "IC1") (pin "20") (pinfunction "TOCAP_20") (pintype "output"))
    )
    (net (code "36") (name "Net-(IC1-XI)") (class "Default")
      (node (ref "C9") (pin "1") (pinfunction "1_1") (pintype "passive"))
      (node (ref "IC1") (pin "30") (pinfunction "XI_30") (pintype "input"))
      (node (ref "R13") (pin "1") (pinfunction "1_1") (pintype "passive"))
      (node (ref "X1") (pin "3") (pinfunction "OUT_3") (pintype "output"))
    )
    (net (code "37") (name "Net-(IC1-XO)") (class "Default")
      (node (ref "C8") (pin "1") (pinfunction "1_1") (pintype "passive"))
      (node (ref "IC1") (pin "31") (pinfunction "XO_31") (pintype "output"))
      (node (ref "R13") (pin "2") (pinfunction "2_2") (pintype "passive"))
      (node (ref "X1") (pin "1") (pinfunction "CON_1") (pintype "input"))
    )
    (net (code "38") (name "Net-(IC2-RUN)") (class "Default")
      (node (ref "IC2") (pin "26") (pinfunction "RUN_26") (pintype "bidirectional"))
      (node (ref "R50") (pin "2") (pinfunction "2_2") (pintype "passive"))
      (node (ref "RESET") (pin "2") (pinfunction "2_2") (pintype "passive"))
    )
    (net (code "39") (name "Net-(IC2-USB_DM)") (class "Default")
      (node (ref "IC2") (pin "46") (pinfunction "USB_DM_46") (pintype "bidirectional"))
      (node (ref "R21") (pin "2") (pinfunction "2_2") (pintype "passive"))
    )
    (net (code "40") (name "Net-(IC2-USB_DP)") (class "Default")
      (node (ref "IC2") (pin "47") (pinfunction "USB_DP_47") (pintype "bidirectional"))
      (node (ref "R22") (pin "2") (pinfunction "2_2") (pintype "passive"))
    )
    (net (code "41") (name "Net-(IC3-+IN)") (class "Default")
      (node (ref "C21") (pin "1") (pinfunction "1_1") (pintype "passive"))
      (node (ref "C22") (pin "1") (pinfunction "1_1") (pintype "passive"))
      (node (ref "IC3") (pin "3") (pinfunction "+IN_3") (pintype "input"))
      (node (ref "R17") (pin "1") (pinfunction "1_1") (pintype "passive"))
      (node (ref "REF1") (pin "1") (pinfunction "C_1") (pintype "passive"))
      (node (ref "VREF") (pin "TP") (pinfunction "P$1_TP") (pintype "bidirectional"))
    )
    (net (code "42") (name "Net-(IC6-A0)") (class "Default")
      (node (ref "IC6") (pin "1") (pinfunction "A0_1") (pintype "bidirectional"))
      (node (ref "R27") (pin "1") (pinfunction "1_1") (pintype "passive"))
      (node (ref "R28") (pin "2") (pinfunction "2_2") (pintype "passive"))
    )
    (net (code "43") (name "Net-(X2-OUT)") (class "Default")
      (node (ref "C20") (pin "1") (pinfunction "1_1") (pintype "passive"))
      (node (ref "R15") (pin "2") (pinfunction "2_2") (pintype "passive"))
      (node (ref "R16") (pin "1") (pinfunction "1_1") (pintype "passive"))
      (node (ref "X2") (pin "3") (pinfunction "OUT_3") (pintype "output"))
    )
    (net (code "44") (name "QSPI_SCLK") (class "Default")
      (node (ref "IC2") (pin "52") (pinfunction "QSPI_SCLK_52") (pintype "bidirectional"))
      (node (ref "IC4") (pin "6") (pinfunction "CLK_6") (pintype "bidirectional"))
    )
    (net (code "45") (name "QSPI_SD0") (class "Default")
      (node (ref "IC2") (pin "53") (pinfunction "QSPI_SD0_53") (pintype "bidirectional"))
      (node (ref "IC4") (pin "5") (pinfunction "DI/IO0_5") (pintype "bidirectional"))
    )
    (net (code "46") (name "QSPI_SD1") (class "Default")
      (node (ref "IC2") (pin "55") (pinfunction "QSPI_SD1_55") (pintype "bidirectional"))
      (node (ref "IC4") (pin "2") (pinfunction "DO/IO1_2") (pintype "bidirectional"))
    )
    (net (code "47") (name "QSPI_SD2") (class "Default")
      (node (ref "IC2") (pin "54") (pinfunction "QSPI_SD2_54") (pintype "bidirectional"))
      (node (ref "IC4") (pin "3") (pinfunction "~{WP}/IO2_3") (pintype "bidirectional"))
    )
    (net (code "48") (name "QSPI_SD3") (class "Default")
      (node (ref "IC2") (pin "51") (pinfunction "QSPI_SD3_51") (pintype "bidirectional"))
      (node (ref "IC4") (pin "7") (pinfunction "~{HOLD}/IO3_7") (pintype "bidirectional"))
    )
    (net (code "49") (name "RCT") (class "Default")
      (node (ref "C1") (pin "1") (pinfunction "1_1") (pintype "passive"))
      (node (ref "ETH1") (pin "5") (pinfunction "RCT_5") (pintype "passive"))
      (node (ref "R5") (pin "1") (pinfunction "1_1") (pintype "passive"))
      (node (ref "R6") (pin "1") (pinfunction "1_1") (pintype "passive"))
    )
    (net (code "50") (name "RDC_RD_N") (class "Default")
      (node (ref "C3") (pin "1") (pinfunction "1_1") (pintype "passive"))
      (node (ref "R4") (pin "2") (pinfunction "2_2") (pintype "passive"))
      (node (ref "R5") (pin "2") (pinfunction "2_2") (pintype "passive"))
    )
    (net (code "51") (name "RDC_RD_P") (class "Default")
      (node (ref "C4") (pin "1") (pinfunction "1_1") (pintype "passive"))
      (node (ref "R3") (pin "2") (pinfunction "2_2") (pintype "passive"))
      (node (ref "R6") (pin "2") (pinfunction "2_2") (pintype "passive"))
    )
    (net (code "52") (name "RD_N") (class "Default")
      (node (ref "C3") (pin "2") (pinfunction "2_2") (pintype "passive"))
      (node (ref "ETH1") (pin "6") (pinfunction "RD-_6") (pintype "passive"))
    )
    (net (code "53") (name "RD_P") (class "Default")
      (node (ref "C4") (pin "2") (pinfunction "2_2") (pintype "passive"))
      (node (ref "ETH1") (pin "4") (pinfunction "RD+_4") (pintype "passive"))
    )
    (net (code "54") (name "RP_XI") (class "Default")
      (node (ref "C19") (pin "1") (pinfunction "1_1") (pintype "passive"))
      (node (ref "IC2") (pin "20") (pinfunction "XIN_20") (pintype "bidirectional"))
      (node (ref "R15") (pin "1") (pinfunction "1_1") (pintype "passive"))
      (node (ref "X2") (pin "1") (pinfunction "CON_1") (pintype "input"))
    )
    (net (code "55") (name "RP_XO") (class "Default")
      (node (ref "IC2") (pin "21") (pinfunction "XOUT_21") (pintype "bidirectional"))
      (node (ref "R16") (pin "2") (pinfunction "2_2") (pintype "passive"))
    )
    (net (code "56") (name "RX_RD_N") (class "Default")
      (node (ref "IC1") (pin "5") (pinfunction "RXN_5") (pintype "input"))
      (node (ref "R4") (pin "1") (pinfunction "1_1") (pintype "passive"))
    )
    (net (code "57") (name "RX_RD_P") (class "Default")
      (node (ref "IC1") (pin "6") (pinfunction "RXP_6") (pintype "input"))
      (node (ref "R3") (pin "1") (pinfunction "1_1") (pintype "passive"))
    )
    (net (code "58") (name "SWCLK") (class "Default")
      (node (ref "DBG2") (pin "1") (pinfunction "P$1_1") (pintype "bidirectional"))
      (node (ref "IC2") (pin "24") (pinfunction "SWCLK_24") (pintype "bidirectional"))
    )
    (net (code "59") (name "SWDIO") (class "Default")
      (node (ref "DBG2") (pin "3") (pinfunction "P$3_3") (pintype "bidirectional"))
      (node (ref "IC2") (pin "25") (pinfunction "SWDIO_25") (pintype "bidirectional"))
    )
    (net (code "60") (name "TCT") (class "Default")
      (node (ref "C2") (pin "1") (pinfunction "1_1") (pintype "passive"))
      (node (ref "ETH1") (pin "2") (pinfunction "TCT_2") (pintype "passive"))
      (node (ref "R40") (pin "1") (pinfunction "1_1") (pintype "passive"))
    )
    (net (code "61") (name "TD_N") (class "Default")
      (node (ref "ETH1") (pin "3") (pinfunction "TD-_3") (pintype "passive"))
      (node (ref "R1") (pin "2") (pinfunction "2_2") (pintype "passive"))
      (node (ref "R8") (pin "1") (pinfunction "1_1") (pintype "passive"))
    )
    (net (code "62") (name "TD_P") (class "Default")
      (node (ref "ETH1") (pin "1") (pinfunction "TD+_1") (pintype "passive"))
      (node (ref "R2") (pin "2") (pinfunction "2_2") (pintype "passive"))
      (node (ref "R7") (pin "1") (pinfunction "1_1") (pintype "passive"))
    )
    (net (code "63") (name "TX_TD_N") (class "Default")
      (node (ref "IC1") (pin "1") (pinfunction "TXN_1") (pintype "output"))
      (node (ref "R1") (pin "1") (pinfunction "1_1") (pintype "passive"))
    )
    (net (code "64") (name "TX_TD_P") (class "Default")
      (node (ref "IC1") (pin "2") (pinfunction "TXP_2") (pintype "output"))
      (node (ref "R2") (pin "1") (pinfunction "1_1") (pintype "passive"))
    )
    (net (code "65") (name "UART0_RX") (class "Default")
      (node (ref "DBG1") (pin "1") (pinfunction "P$1_1") (pintype "bidirectional"))
      (node (ref "IC2") (pin "2") (pinfunction "GPIO0_2") (pintype "bidirectional"))
      (node (ref "RELAYBOARD") (pin "10") (pinfunction "10_10") (pintype "passive"))
    )
    (net (code "66") (name "UART0_TX") (class "Default")
      (node (ref "DBG1") (pin "3") (pinfunction "P$3_3") (pintype "bidirectional"))
      (node (ref "IC2") (pin "3") (pinfunction "GPIO1_3") (pintype "bidirectional"))
      (node (ref "RELAYBOARD") (pin "11") (pinfunction "11_11") (pintype "passive"))
    )
    (net (code "67") (name "USB_BOOT") (class "Default")
      (node (ref "BOOT") (pin "1") (pinfunction "1_1") (pintype "passive"))
      (node (ref "R19") (pin "1") (pinfunction "1_1") (pintype "passive"))
    )
    (net (code "68") (name "USB_SHIELD") (class "Default")
      (node (ref "C54") (pin "1") (pinfunction "1_1") (pintype "passive"))
      (node (ref "R39") (pin "1") (pinfunction "1_1") (pintype "passive"))
      (node (ref "USBC") (pin "S1") (pinfunction "SHIELD_S1") (pintype "passive"))
      (node (ref "USBC") (pin "S2") (pinfunction "SHIELD_S2") (pintype "passive"))
      (node (ref "USBC") (pin "S3") (pinfunction "SHIELD_S3") (pintype "passive"))
      (node (ref "USBC") (pin "S4") (pinfunction "SHIELD_S4") (pintype "passive"))
    )
    (net (code "69") (name "VBUS") (class "Default")
      (node (ref "C26") (pin "1") (pinfunction "1_1") (pintype "passive"))
      (node (ref "C27") (pin "1") (pinfunction "1_1") (pintype "passive"))
      (node (ref "C36") (pin "1") (pinfunction "1_1") (pintype "passive"))
      (node (ref "C40") (pin "1") (pinfunction "1_1") (pintype "passive"))
      (node (ref "ESD1") (pin "4") (pinfunction "C3_4") (pintype "bidirectional"))
      (node (ref "IC5") (pin "1") (pinfunction "VIN_1") (pintype "bidirectional"))
      (node (ref "IC5") (pin "3") (pinfunction "EN_3") (pintype "bidirectional"))
      (node (ref "R20") (pin "1") (pinfunction "1_1") (pintype "passive"))
      (node (ref "R25") (pin "1") (pinfunction "1_1") (pintype "passive"))
      (node (ref "USBC") (pin "A4") (pinfunction "VBUS_A4") (pintype "passive"))
      (node (ref "USBC") (pin "A9") (pinfunction "VBUS1_A9") (pintype "passive"))
      (node (ref "USBC") (pin "B4") (pinfunction "VBUS3_B4") (pintype "passive"))
      (node (ref "USBC") (pin "B9") (pinfunction "VBUS2_B9") (pintype "passive"))
      (node (ref "VBUS") (pin "TP") (pinfunction "P$1_TP") (pintype "bidirectional"))
    )
    (net (code "70") (name "W5500_MISO") (class "Default")
      (node (ref "IC1") (pin "34") (pinfunction "MISO_34") (pintype "output"))
      (node (ref "IC2") (pin "27") (pinfunction "GPIO16_27") (pintype "bidirectional"))
    )
    (net (code "71") (name "W5500_MOSI") (class "Default")
      (node (ref "IC1") (pin "35") (pinfunction "MOSI_35") (pintype "input"))
      (node (ref "IC2") (pin "30") (pinfunction "GPIO19_30") (pintype "bidirectional"))
    )
    (net (code "72") (name "W5500_SCK") (class "Default")
      (node (ref "IC1") (pin "33") (pinfunction "SCLK_33") (pintype "input"))
      (node (ref "IC2") (pin "29") (pinfunction "GPIO18_29") (pintype "bidirectional"))
    )
    (net (code "73") (name "unconnected-(IC1-DNC-Pad7)") (class "Default")
      (node (ref "IC1") (pin "7") (pinfunction "DNC_7") (pintype "bidirectional"))
    )
    (net (code "74") (name "unconnected-(IC1-DUPLED-Pad26)") (class "Default")
      (node (ref "IC1") (pin "26") (pinfunction "DUPLED_26") (pintype "output"))
    )
    (net (code "75") (name "unconnected-(IC1-RSVD1-Pad23)") (class "Default")
      (node (ref "IC1") (pin "23") (pinfunction "RSVD1_23") (pintype "input"))
    )
    (net (code "76") (name "unconnected-(IC1-RSVD2-Pad38)") (class "Default")
      (node (ref "IC1") (pin "38") (pinfunction "RSVD2_38") (pintype "input"))
    )
    (net (code "77") (name "unconnected-(IC1-RSVD3-Pad39)") (class "Default")
      (node (ref "IC1") (pin "39") (pinfunction "RSVD3_39") (pintype "input"))
    )
    (net (code "78") (name "unconnected-(IC1-RSVD4-Pad40)") (class "Default")
      (node (ref "IC1") (pin "40") (pinfunction "RSVD4_40") (pintype "input"))
    )
    (net (code "79") (name "unconnected-(IC1-RSVD5-Pad41)") (class "Default")
      (node (ref "IC1") (pin "41") (pinfunction "RSVD5_41") (pintype "input"))
    )
    (net (code "80") (name "unconnected-(IC1-RSVD6-Pad42)") (class "Default")
      (node (ref "IC1") (pin "42") (pinfunction "RSVD6_42") (pintype "input"))
    )
    (net (code "81") (name "unconnected-(IC1-SPDLED-Pad24)") (class "Default")
      (node (ref "IC1") (pin "24") (pinfunction "SPDLED_24") (pintype "output"))
    )
    (net (code "82") (name "unconnected-(IC1-VBG-Pad18)") (class "Default")
      (node (ref "IC1") (pin "18") (pinfunction "VBG_18") (pintype "output"))
    )
    (net (code "83") (name "unconnected-(IC2-GPIO25-Pad37)") (class "Default")
      (node (ref "IC2") (pin "37") (pinfunction "GPIO25_37") (pintype "bidirectional"))
    )
    (net (code "84") (name "unconnected-(IC2-GPIO27{slash}ADC1-Pad39)") (class "Default")
      (node (ref "IC2") (pin "39") (pinfunction "GPIO27/ADC1_39") (pintype "bidirectional"))
    )
    (net (code "85") (name "unconnected-(IC2-GPIO28{slash}ADC2-Pad40)") (class "Default")
      (node (ref "IC2") (pin "40") (pinfunction "GPIO28/ADC2_40") (pintype "bidirectional"))
    )
    (net (code "86") (name "unconnected-(IC5-NC-Pad4)") (class "Default")
      (node (ref "IC5") (pin "4") (pinfunction "NC_4") (pintype "bidirectional"))
    )
    (net (code "87") (name "unconnected-(R30-Pad5)") (class "Default")
      (node (ref "R30") (pin "5") (pinfunction "5_5") (pintype "passive"))
    )
    (net (code "88") (name "unconnected-(RELAYBOARD-Pad17)") (class "Default")
      (node (ref "RELAYBOARD") (pin "17") (pinfunction "17_17") (pintype "passive"))
    )
    (net (code "89") (name "unconnected-(RELAYBOARD-Pad18)") (class "Default")
      (node (ref "RELAYBOARD") (pin "18") (pinfunction "18_18") (pintype "passive"))
    )
    (net (code "90") (name "unconnected-(RELAYBOARD-Pad19)") (class "Default")
      (node (ref "RELAYBOARD") (pin "19") (pinfunction "19_19") (pintype "passive"))
    )
    (net (code "91") (name "unconnected-(RELAYBOARD-Pad20)") (class "Default")
      (node (ref "RELAYBOARD") (pin "20") (pinfunction "20_20") (pintype "passive"))
    )
    (net (code "92") (name "unconnected-(USBC-SBU1-PadA8)") (class "Default")
      (node (ref "USBC") (pin "A8") (pinfunction "SBU1_A8") (pintype "passive"))
    )
    (net (code "93") (name "unconnected-(USBC-SBU2-PadB8)") (class "Default")
      (node (ref "USBC") (pin "B8") (pinfunction "SBU2_B8") (pintype "passive"))
    )
    (net (code "94") (name "~{ACT}") (class "Default")
      (node (ref "IC1") (pin "27") (pinfunction "ACTLED_27") (pintype "output"))
      (node (ref "R10") (pin "1") (pinfunction "1_1") (pintype "passive"))
    )
    (net (code "95") (name "~{LINK}") (class "Default")
      (node (ref "IC1") (pin "25") (pinfunction "LINKLED_25") (pintype "output"))
      (node (ref "R9") (pin "1") (pinfunction "1_1") (pintype "passive"))
    )
    (net (code "96") (name "~{QSPI_SS}") (class "Default")
      (node (ref "IC2") (pin "56") (pinfunction "QSPI_SS_N_56") (pintype "bidirectional"))
      (node (ref "IC4") (pin "1") (pinfunction "~{CS}_1") (pintype "bidirectional"))
      (node (ref "R18") (pin "1") (pinfunction "1_1") (pintype "passive"))
      (node (ref "R19") (pin "2") (pinfunction "2_2") (pintype "passive"))
    )
    (net (code "97") (name "~{W5500_CS}") (class "Default")
      (node (ref "IC1") (pin "32") (pinfunction "~{SCSN}_32") (pintype "input"))
      (node (ref "IC2") (pin "28") (pinfunction "GPIO17_28") (pintype "bidirectional"))
    )
    (net (code "98") (name "~{W5500_INT}") (class "Default")
      (node (ref "IC1") (pin "36") (pinfunction "~{INTN}_36") (pintype "input"))
      (node (ref "IC2") (pin "32") (pinfunction "GPIO21_32") (pintype "bidirectional"))
    )
    (net (code "99") (name "~{W5500_RST}") (class "Default")
      (node (ref "IC1") (pin "37") (pinfunction "~{RSTN}_37") (pintype "input"))
      (node (ref "IC2") (pin "31") (pinfunction "GPIO20_31") (pintype "bidirectional"))
      (node (ref "R14") (pin "1") (pinfunction "1_1") (pintype "passive"))
    )
  )
)
